# 10_POWER.net
KiCad netlist of a schematic drawn in Altium Designer
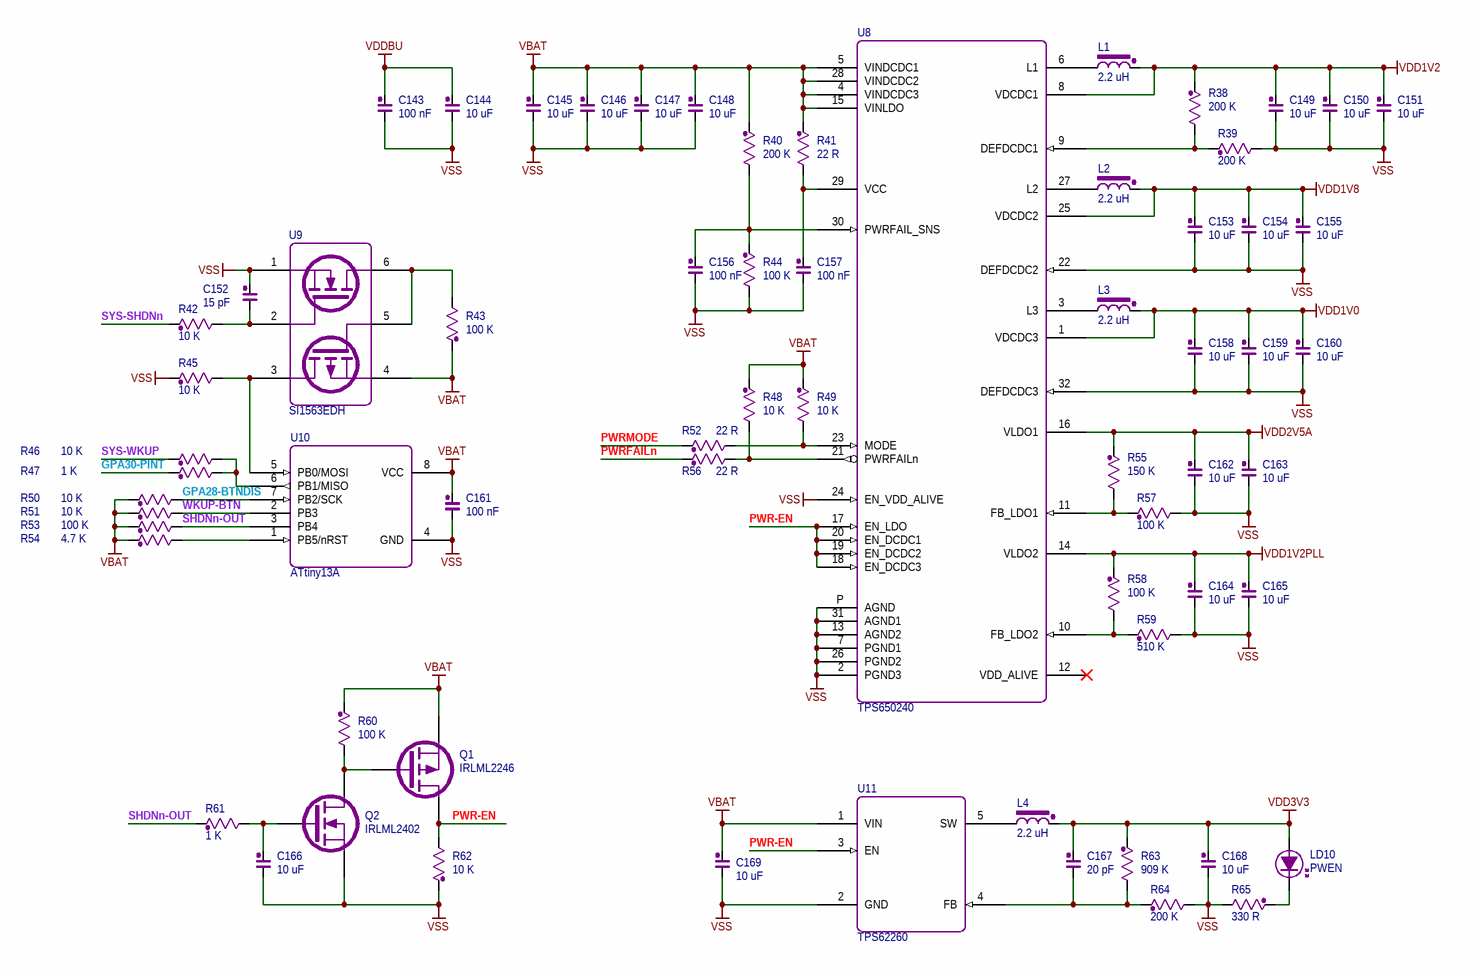
[diagram p0: 10_POWER.SchDoc]

(export (version "E")
  (design (tool "Eeschema 10.0.6"))
  (components
    (comp (ref "C143")
      (value "100 nF")
      (footprint "0402A1")
      (description "Normal Capacitor")
      (fields
        (field (name "PARTNUMBER") "0")
        (field (name "PUBLISHER") "Cowin")
        (field (name "DESIGNER") "shyul")
      )
      (libsource (lib "Basc_1_Passive") (part "CAP"))
    )
    (comp (ref "C144")
      (value "10 uF")
      (footprint "0603A1")
      (description "Normal Capacitor")
      (fields
        (field (name "PARTNUMBER") "0")
        (field (name "PUBLISHER") "Cowin")
        (field (name "DESIGNER") "shyul")
      )
      (libsource (lib "Basc_1_Passive") (part "CAP"))
    )
    (comp (ref "C145")
      (value "10 uF")
      (footprint "0603A1")
      (description "Normal Capacitor")
      (fields
        (field (name "PARTNUMBER") "0")
        (field (name "PUBLISHER") "Cowin")
        (field (name "DESIGNER") "shyul")
      )
      (libsource (lib "Basc_1_Passive") (part "CAP"))
    )
    (comp (ref "C146")
      (value "10 uF")
      (footprint "0603A1")
      (description "Normal Capacitor")
      (fields
        (field (name "PARTNUMBER") "0")
        (field (name "PUBLISHER") "Cowin")
        (field (name "DESIGNER") "shyul")
      )
      (libsource (lib "Basc_1_Passive") (part "CAP"))
    )
    (comp (ref "C147")
      (value "10 uF")
      (footprint "0603A1")
      (description "Normal Capacitor")
      (fields
        (field (name "PARTNUMBER") "0")
        (field (name "PUBLISHER") "Cowin")
        (field (name "DESIGNER") "shyul")
      )
      (libsource (lib "Basc_1_Passive") (part "CAP"))
    )
    (comp (ref "C148")
      (value "10 uF")
      (footprint "0603A1")
      (description "Normal Capacitor")
      (fields
        (field (name "PARTNUMBER") "0")
        (field (name "PUBLISHER") "Cowin")
        (field (name "DESIGNER") "shyul")
      )
      (libsource (lib "Basc_1_Passive") (part "CAP"))
    )
    (comp (ref "C149")
      (value "10 uF")
      (footprint "0603A1")
      (description "Normal Capacitor")
      (fields
        (field (name "PARTNUMBER") "0")
        (field (name "PUBLISHER") "Cowin")
        (field (name "DESIGNER") "shyul")
      )
      (libsource (lib "Basc_1_Passive") (part "CAP"))
    )
    (comp (ref "C150")
      (value "10 uF")
      (footprint "0603A1")
      (description "Normal Capacitor")
      (fields
        (field (name "PARTNUMBER") "0")
        (field (name "PUBLISHER") "Cowin")
        (field (name "DESIGNER") "shyul")
      )
      (libsource (lib "Basc_1_Passive") (part "CAP"))
    )
    (comp (ref "C151")
      (value "10 uF")
      (footprint "0603A1")
      (description "Normal Capacitor")
      (fields
        (field (name "PARTNUMBER") "0")
        (field (name "PUBLISHER") "Cowin")
        (field (name "DESIGNER") "shyul")
      )
      (libsource (lib "Basc_1_Passive") (part "CAP"))
    )
    (comp (ref "C152")
      (value "15 pF")
      (footprint "0402A1")
      (description "Normal Capacitor")
      (fields
        (field (name "PARTNUMBER") "0")
        (field (name "PUBLISHER") "Cowin")
        (field (name "DESIGNER") "shyul")
      )
      (libsource (lib "Basc_1_Passive") (part "CAP"))
    )
    (comp (ref "C153")
      (value "10 uF")
      (footprint "0603A1")
      (description "Normal Capacitor")
      (fields
        (field (name "PARTNUMBER") "0")
        (field (name "PUBLISHER") "Cowin")
        (field (name "DESIGNER") "shyul")
      )
      (libsource (lib "Basc_1_Passive") (part "CAP"))
    )
    (comp (ref "C154")
      (value "10 uF")
      (footprint "0603A1")
      (description "Normal Capacitor")
      (fields
        (field (name "PARTNUMBER") "0")
        (field (name "PUBLISHER") "Cowin")
        (field (name "DESIGNER") "shyul")
      )
      (libsource (lib "Basc_1_Passive") (part "CAP"))
    )
    (comp (ref "C155")
      (value "10 uF")
      (footprint "0603A1")
      (description "Normal Capacitor")
      (fields
        (field (name "PARTNUMBER") "0")
        (field (name "PUBLISHER") "Cowin")
        (field (name "DESIGNER") "shyul")
      )
      (libsource (lib "Basc_1_Passive") (part "CAP"))
    )
    (comp (ref "C156")
      (value "100 nF")
      (footprint "0402A1")
      (description "Normal Capacitor")
      (fields
        (field (name "PARTNUMBER") "0")
        (field (name "PUBLISHER") "Cowin")
        (field (name "DESIGNER") "shyul")
      )
      (libsource (lib "Basc_1_Passive") (part "CAP"))
    )
    (comp (ref "C157")
      (value "100 nF")
      (footprint "0402A1")
      (description "Normal Capacitor")
      (fields
        (field (name "PARTNUMBER") "0")
        (field (name "PUBLISHER") "Cowin")
        (field (name "DESIGNER") "shyul")
      )
      (libsource (lib "Basc_1_Passive") (part "CAP"))
    )
    (comp (ref "C158")
      (value "10 uF")
      (footprint "0603A1")
      (description "Normal Capacitor")
      (fields
        (field (name "PARTNUMBER") "0")
        (field (name "PUBLISHER") "Cowin")
        (field (name "DESIGNER") "shyul")
      )
      (libsource (lib "Basc_1_Passive") (part "CAP"))
    )
    (comp (ref "C159")
      (value "10 uF")
      (footprint "0603A1")
      (description "Normal Capacitor")
      (fields
        (field (name "PARTNUMBER") "0")
        (field (name "PUBLISHER") "Cowin")
        (field (name "DESIGNER") "shyul")
      )
      (libsource (lib "Basc_1_Passive") (part "CAP"))
    )
    (comp (ref "C160")
      (value "10 uF")
      (footprint "0603A1")
      (description "Normal Capacitor")
      (fields
        (field (name "PARTNUMBER") "0")
        (field (name "PUBLISHER") "Cowin")
        (field (name "DESIGNER") "shyul")
      )
      (libsource (lib "Basc_1_Passive") (part "CAP"))
    )
    (comp (ref "C161")
      (value "100 nF")
      (footprint "0402A1")
      (description "Normal Capacitor")
      (fields
        (field (name "PARTNUMBER") "0")
        (field (name "PUBLISHER") "Cowin")
        (field (name "DESIGNER") "shyul")
      )
      (libsource (lib "Basc_1_Passive") (part "CAP"))
    )
    (comp (ref "C162")
      (value "10 uF")
      (footprint "0603A1")
      (description "Normal Capacitor")
      (fields
        (field (name "PARTNUMBER") "0")
        (field (name "PUBLISHER") "Cowin")
        (field (name "DESIGNER") "shyul")
      )
      (libsource (lib "Basc_1_Passive") (part "CAP"))
    )
    (comp (ref "C163")
      (value "10 uF")
      (footprint "0603A1")
      (description "Normal Capacitor")
      (fields
        (field (name "PARTNUMBER") "0")
        (field (name "PUBLISHER") "Cowin")
        (field (name "DESIGNER") "shyul")
      )
      (libsource (lib "Basc_1_Passive") (part "CAP"))
    )
    (comp (ref "C164")
      (value "10 uF")
      (footprint "0603A1")
      (description "Normal Capacitor")
      (fields
        (field (name "PARTNUMBER") "0")
        (field (name "PUBLISHER") "Cowin")
        (field (name "DESIGNER") "shyul")
      )
      (libsource (lib "Basc_1_Passive") (part "CAP"))
    )
    (comp (ref "C165")
      (value "10 uF")
      (footprint "0603A1")
      (description "Normal Capacitor")
      (fields
        (field (name "PARTNUMBER") "0")
        (field (name "PUBLISHER") "Cowin")
        (field (name "DESIGNER") "shyul")
      )
      (libsource (lib "Basc_1_Passive") (part "CAP"))
    )
    (comp (ref "C166")
      (value "10 uF")
      (footprint "0603A1")
      (description "Normal Capacitor")
      (fields
        (field (name "PARTNUMBER") "0")
        (field (name "PUBLISHER") "Cowin")
        (field (name "DESIGNER") "shyul")
      )
      (libsource (lib "Basc_1_Passive") (part "CAP"))
    )
    (comp (ref "C167")
      (value "20 pF")
      (footprint "0402A1")
      (description "Normal Capacitor")
      (fields
        (field (name "PARTNUMBER") "0")
        (field (name "PUBLISHER") "Cowin")
        (field (name "DESIGNER") "shyul")
      )
      (libsource (lib "Basc_1_Passive") (part "CAP"))
    )
    (comp (ref "C168")
      (value "10 uF")
      (footprint "0603A1")
      (description "Normal Capacitor")
      (fields
        (field (name "PARTNUMBER") "0")
        (field (name "PUBLISHER") "Cowin")
        (field (name "DESIGNER") "shyul")
      )
      (libsource (lib "Basc_1_Passive") (part "CAP"))
    )
    (comp (ref "C169")
      (value "10 uF")
      (footprint "0603A1")
      (description "Normal Capacitor")
      (fields
        (field (name "PARTNUMBER") "0")
        (field (name "PUBLISHER") "Cowin")
        (field (name "DESIGNER") "shyul")
      )
      (libsource (lib "Basc_1_Passive") (part "CAP"))
    )
    (comp (ref "L1")
      (value "2.2 uH")
      (footprint "COIL_S_3X3")
      (description "Power Coil Inductor")
      (fields
        (field (name "PARTNUMBER") "LPD3015-222ML")
        (field (name "PUBLISHER") "Cowin")
        (field (name "DESIGNER") "shyul")
      )
      (libsource (lib "Basc_1_Passive") (part "COIL"))
    )
    (comp (ref "L2")
      (value "2.2 uH")
      (footprint "COIL_S_3X3")
      (description "Power Coil Inductor")
      (fields
        (field (name "PARTNUMBER") "LPD3015-222ML")
        (field (name "PUBLISHER") "Cowin")
        (field (name "DESIGNER") "shyul")
      )
      (libsource (lib "Basc_1_Passive") (part "COIL"))
    )
    (comp (ref "L3")
      (value "2.2 uH")
      (footprint "COIL_S_3X3")
      (description "Power Coil Inductor")
      (fields
        (field (name "PARTNUMBER") "LPD3015-222ML")
        (field (name "PUBLISHER") "Cowin")
        (field (name "DESIGNER") "shyul")
      )
      (libsource (lib "Basc_1_Passive") (part "COIL"))
    )
    (comp (ref "L4")
      (value "2.2 uH")
      (footprint "COIL_S_3X3")
      (description "Power Coil Inductor")
      (fields
        (field (name "PARTNUMBER") "LPD3015-222ML")
        (field (name "PUBLISHER") "Cowin")
        (field (name "DESIGNER") "shyul")
      )
      (libsource (lib "Basc_1_Passive") (part "COIL"))
    )
    (comp (ref "LD10")
      (value "PWEN")
      (footprint "0603LD")
      (description "LED Single")
      (fields
        (field (name "PARTNUMBER") "0")
        (field (name "DESIGNER") "shyul")
        (field (name "PUBLISHER") "Cowin")
      )
      (libsource (lib "Basc_4_Other") (part "LED"))
    )
    (comp (ref "Q1")
      (value "IRLML2246")
      (footprint "SOT-23-3")
      (description "P Channel Enhancement MOSFET")
      (fields
        (field (name "PARTNUMBER") "IRLML2246TRPbF")
        (field (name "PUBLISHER") "Cowin")
        (field (name "DESIGNER") "shyul")
      )
      (libsource (lib "Basc_3_Diode_Transistor") (part "MOSFET_EP"))
    )
    (comp (ref "Q2")
      (value "IRLML2402")
      (footprint "SOT-23-3")
      (description "N Channel Enhancement MOSFET")
      (fields
        (field (name "PARTNUMBER") "IRLML2402GPbF")
        (field (name "PUBLISHER") "Cowin")
        (field (name "DESIGNER") "shyul")
      )
      (libsource (lib "Basc_3_Diode_Transistor") (part "MOSFET_EN"))
    )
    (comp (ref "R38")
      (value "200 K")
      (footprint "0402A2")
      (description "Normal Resistor")
      (fields
        (field (name "PARTNUMBER") "0")
        (field (name "DESIGNER") "shyul")
        (field (name "PUBLISHER") "Cowin")
      )
      (libsource (lib "Basc_1_Passive") (part "RES"))
    )
    (comp (ref "R39")
      (value "200 K")
      (footprint "0402A2")
      (description "Normal Resistor")
      (fields
        (field (name "PARTNUMBER") "0")
        (field (name "DESIGNER") "shyul")
        (field (name "PUBLISHER") "Cowin")
      )
      (libsource (lib "Basc_1_Passive") (part "RES"))
    )
    (comp (ref "R40")
      (value "200 K")
      (footprint "0402A2")
      (description "Normal Resistor")
      (fields
        (field (name "PARTNUMBER") "0")
        (field (name "DESIGNER") "shyul")
        (field (name "PUBLISHER") "Cowin")
      )
      (libsource (lib "Basc_1_Passive") (part "RES"))
    )
    (comp (ref "R41")
      (value "22 R")
      (footprint "0402A2")
      (description "Normal Resistor")
      (fields
        (field (name "PARTNUMBER") "0")
        (field (name "DESIGNER") "shyul")
        (field (name "PUBLISHER") "Cowin")
      )
      (libsource (lib "Basc_1_Passive") (part "RES"))
    )
    (comp (ref "R42")
      (value "10 K")
      (footprint "0402A2")
      (description "Normal Resistor")
      (fields
        (field (name "PARTNUMBER") "0")
        (field (name "DESIGNER") "shyul")
        (field (name "PUBLISHER") "Cowin")
      )
      (libsource (lib "Basc_1_Passive") (part "RES"))
    )
    (comp (ref "R43")
      (value "100 K")
      (footprint "0402A2")
      (description "Normal Resistor")
      (fields
        (field (name "PARTNUMBER") "0")
        (field (name "DESIGNER") "shyul")
        (field (name "PUBLISHER") "Cowin")
      )
      (libsource (lib "Basc_1_Passive") (part "RES"))
    )
    (comp (ref "R44")
      (value "100 K")
      (footprint "0402A2")
      (description "Normal Resistor")
      (fields
        (field (name "PARTNUMBER") "0")
        (field (name "DESIGNER") "shyul")
        (field (name "PUBLISHER") "Cowin")
      )
      (libsource (lib "Basc_1_Passive") (part "RES"))
    )
    (comp (ref "R45")
      (value "10 K")
      (footprint "0402A2")
      (description "Normal Resistor")
      (fields
        (field (name "PARTNUMBER") "0")
        (field (name "DESIGNER") "shyul")
        (field (name "PUBLISHER") "Cowin")
      )
      (libsource (lib "Basc_1_Passive") (part "RES"))
    )
    (comp (ref "R46")
      (value "10 K")
      (footprint "0402A2")
      (description "Normal Resistor")
      (fields
        (field (name "PARTNUMBER") "0")
        (field (name "DESIGNER") "shyul")
        (field (name "PUBLISHER") "Cowin")
      )
      (libsource (lib "Basc_1_Passive") (part "RES"))
    )
    (comp (ref "R47")
      (value "1 K")
      (footprint "0402A2")
      (description "Normal Resistor")
      (fields
        (field (name "PARTNUMBER") "0")
        (field (name "DESIGNER") "shyul")
        (field (name "PUBLISHER") "Cowin")
      )
      (libsource (lib "Basc_1_Passive") (part "RES"))
    )
    (comp (ref "R48")
      (value "10 K")
      (footprint "0402A2")
      (description "Normal Resistor")
      (fields
        (field (name "PARTNUMBER") "0")
        (field (name "DESIGNER") "shyul")
        (field (name "PUBLISHER") "Cowin")
      )
      (libsource (lib "Basc_1_Passive") (part "RES"))
    )
    (comp (ref "R49")
      (value "10 K")
      (footprint "0402A2")
      (description "Normal Resistor")
      (fields
        (field (name "PARTNUMBER") "0")
        (field (name "DESIGNER") "shyul")
        (field (name "PUBLISHER") "Cowin")
      )
      (libsource (lib "Basc_1_Passive") (part "RES"))
    )
    (comp (ref "R50")
      (value "10 K")
      (footprint "0402A2")
      (description "Normal Resistor")
      (fields
        (field (name "PARTNUMBER") "0")
        (field (name "DESIGNER") "shyul")
        (field (name "PUBLISHER") "Cowin")
      )
      (libsource (lib "Basc_1_Passive") (part "RES"))
    )
    (comp (ref "R51")
      (value "10 K")
      (footprint "0402A2")
      (description "Normal Resistor")
      (fields
        (field (name "PARTNUMBER") "0")
        (field (name "DESIGNER") "shyul")
        (field (name "PUBLISHER") "Cowin")
      )
      (libsource (lib "Basc_1_Passive") (part "RES"))
    )
    (comp (ref "R52")
      (value "22 R")
      (footprint "0402A2")
      (description "Normal Resistor")
      (fields
        (field (name "PARTNUMBER") "0")
        (field (name "DESIGNER") "shyul")
        (field (name "PUBLISHER") "Cowin")
      )
      (libsource (lib "Basc_1_Passive") (part "RES"))
    )
    (comp (ref "R53")
      (value "100 K")
      (footprint "0402A2")
      (description "Normal Resistor")
      (fields
        (field (name "PARTNUMBER") "0")
        (field (name "DESIGNER") "shyul")
        (field (name "PUBLISHER") "Cowin")
      )
      (libsource (lib "Basc_1_Passive") (part "RES"))
    )
    (comp (ref "R54")
      (value "4.7 K")
      (footprint "0402A2")
      (description "Normal Resistor")
      (fields
        (field (name "PARTNUMBER") "0")
        (field (name "DESIGNER") "shyul")
        (field (name "PUBLISHER") "Cowin")
      )
      (libsource (lib "Basc_1_Passive") (part "RES"))
    )
    (comp (ref "R55")
      (value "150 K")
      (footprint "0402A2")
      (description "Normal Resistor")
      (fields
        (field (name "PARTNUMBER") "0")
        (field (name "DESIGNER") "shyul")
        (field (name "PUBLISHER") "Cowin")
      )
      (libsource (lib "Basc_1_Passive") (part "RES"))
    )
    (comp (ref "R56")
      (value "22 R")
      (footprint "0402A2")
      (description "Normal Resistor")
      (fields
        (field (name "PARTNUMBER") "0")
        (field (name "DESIGNER") "shyul")
        (field (name "PUBLISHER") "Cowin")
      )
      (libsource (lib "Basc_1_Passive") (part "RES"))
    )
    (comp (ref "R57")
      (value "100 K")
      (footprint "0402A2")
      (description "Normal Resistor")
      (fields
        (field (name "PARTNUMBER") "0")
        (field (name "DESIGNER") "shyul")
        (field (name "PUBLISHER") "Cowin")
      )
      (libsource (lib "Basc_1_Passive") (part "RES"))
    )
    (comp (ref "R58")
      (value "100 K")
      (footprint "0402A2")
      (description "Normal Resistor")
      (fields
        (field (name "PARTNUMBER") "0")
        (field (name "DESIGNER") "shyul")
        (field (name "PUBLISHER") "Cowin")
      )
      (libsource (lib "Basc_1_Passive") (part "RES"))
    )
    (comp (ref "R59")
      (value "510 K")
      (footprint "0402A2")
      (description "Normal Resistor")
      (fields
        (field (name "PARTNUMBER") "0")
        (field (name "DESIGNER") "shyul")
        (field (name "PUBLISHER") "Cowin")
      )
      (libsource (lib "Basc_1_Passive") (part "RES"))
    )
    (comp (ref "R60")
      (value "100 K")
      (footprint "0402A2")
      (description "Normal Resistor")
      (fields
        (field (name "PARTNUMBER") "0")
        (field (name "DESIGNER") "shyul")
        (field (name "PUBLISHER") "Cowin")
      )
      (libsource (lib "Basc_1_Passive") (part "RES"))
    )
    (comp (ref "R61")
      (value "1 K")
      (footprint "0402A2")
      (description "Normal Resistor")
      (fields
        (field (name "PARTNUMBER") "0")
        (field (name "DESIGNER") "shyul")
        (field (name "PUBLISHER") "Cowin")
      )
      (libsource (lib "Basc_1_Passive") (part "RES"))
    )
    (comp (ref "R62")
      (value "10 K")
      (footprint "0402A2")
      (description "Normal Resistor")
      (fields
        (field (name "PARTNUMBER") "0")
        (field (name "DESIGNER") "shyul")
        (field (name "PUBLISHER") "Cowin")
      )
      (libsource (lib "Basc_1_Passive") (part "RES"))
    )
    (comp (ref "R63")
      (value "909 K")
      (footprint "0402A2")
      (description "Normal Resistor")
      (fields
        (field (name "PARTNUMBER") "0")
        (field (name "DESIGNER") "shyul")
        (field (name "PUBLISHER") "Cowin")
      )
      (libsource (lib "Basc_1_Passive") (part "RES"))
    )
    (comp (ref "R64")
      (value "200 K")
      (footprint "0402A2")
      (description "Normal Resistor")
      (fields
        (field (name "PARTNUMBER") "0")
        (field (name "DESIGNER") "shyul")
        (field (name "PUBLISHER") "Cowin")
      )
      (libsource (lib "Basc_1_Passive") (part "RES"))
    )
    (comp (ref "R65")
      (value "330 R")
      (footprint "0402A2")
      (description "Normal Resistor")
      (fields
        (field (name "PARTNUMBER") "0")
        (field (name "DESIGNER") "shyul")
        (field (name "PUBLISHER") "Cowin")
      )
      (libsource (lib "Basc_1_Passive") (part "RES"))
    )
    (comp (ref "U8")
      (value "TPS650240")
      (footprint "QFN-5-32")
      (description "Embedded Power Management IC")
      (fields
        (field (name "PARTNUMBER") "TPS650240RHBT")
        (field (name "PUBLISHER") "Cowin")
        (field (name "DESIGNER") "shyul")
      )
      (libsource (lib "PCB_XEM-S91") (part "TPS650240"))
    )
    (comp (ref "U9")
      (value "SI1563EDH")
      (footprint "SOT-363")
      (description "Complementary MOSFET")
      (fields (field (name "PUBLISHER") "Cowin") (field (name "DESIGNER") "shyul"))
      (libsource (lib "PCB_XEM-S91") (part "SI1563EDH"))
    )
    (comp (ref "U10")
      (value "ATtiny13A")
      (footprint "SOIC-8W")
      (description "Atmel SPI Flash")
      (fields
        (field (name "PARTNUMBER") "ATtiny13A-SH")
        (field (name "PUBLISHER") "Cowin")
        (field (name "DESIGNER") "shyul")
      )
      (libsource (lib "PCB_XEM-S91") (part "ATtiny13A"))
    )
    (comp (ref "U11")
      (value "TPS62260")
      (footprint "SOT-23-5")
      (description "Simple Switch 600mA Adjustable")
      (fields
        (field (name "PARTNUMBER") "TPS62260DDCR")
        (field (name "PUBLISHER") "Cowin")
        (field (name "DESIGNER") "shyul")
      )
      (libsource (lib "PCB_XEM-S91") (part "TPS62260"))
    )
  )
  (nets
    (net (code "1") (name "/GPA28-BTNDIS") (class "Default")
      (node (ref "R50") (pin "1") (pinfunction "1_1") (pintype "passive"))
      (node (ref "U10") (pin "7") (pinfunction "PB2/SCK_7") (pintype "input"))
    )
    (net (code "2") (name "/GPA30-PINT") (class "Default")
      (node (ref "R47") (pin "2") (pinfunction "2_2") (pintype "passive"))
    )
    (net (code "3") (name "/PWR-EN") (class "Default")
      (node (ref "Q1") (pin "2") (pinfunction "D_2") (pintype "passive"))
      (node (ref "R62") (pin "1") (pinfunction "1_1") (pintype "passive"))
      (node (ref "U11") (pin "3") (pinfunction "EN_3") (pintype "input"))
      (node (ref "U8") (pin "17") (pinfunction "EN_LDO_17") (pintype "input"))
      (node (ref "U8") (pin "18") (pinfunction "EN_DCDC3_18") (pintype "input"))
      (node (ref "U8") (pin "19") (pinfunction "EN_DCDC2_19") (pintype "input"))
      (node (ref "U8") (pin "20") (pinfunction "EN_DCDC1_20") (pintype "input"))
    )
    (net (code "4") (name "/PWRFAILn") (class "Default")
      (node (ref "R56") (pin "2") (pinfunction "2_2") (pintype "passive"))
    )
    (net (code "5") (name "/PWRMODE") (class "Default")
      (node (ref "R52") (pin "2") (pinfunction "2_2") (pintype "passive"))
    )
    (net (code "6") (name "/SHDNn-OUT") (class "Default")
      (node (ref "R53") (pin "1") (pinfunction "1_1") (pintype "passive"))
      (node (ref "R61") (pin "2") (pinfunction "2_2") (pintype "passive"))
      (node (ref "U10") (pin "3") (pinfunction "PB4_3") (pintype "passive"))
    )
    (net (code "7") (name "/SYS-SHDNn") (class "Default")
      (node (ref "R42") (pin "2") (pinfunction "2_2") (pintype "passive"))
    )
    (net (code "8") (name "/SYS-WKUP") (class "Default")
      (node (ref "R46") (pin "2") (pinfunction "2_2") (pintype "passive"))
    )
    (net (code "9") (name "/WKUP-BTN") (class "Default")
      (node (ref "R51") (pin "1") (pinfunction "1_1") (pintype "passive"))
      (node (ref "U10") (pin "2") (pinfunction "PB3_2") (pintype "passive"))
    )
    (net (code "10") (name "Net-(C152-Pad1)") (class "Default")
      (node (ref "C152") (pin "1") (pinfunction "1_1") (pintype "passive"))
      (node (ref "R42") (pin "1") (pinfunction "1_1") (pintype "passive"))
      (node (ref "U9") (pin "2") (pinfunction "2_2") (pintype "passive"))
    )
    (net (code "11") (name "Net-(LD10-Pad1)") (class "Default")
      (node (ref "LD10") (pin "1") (pinfunction "1_1") (pintype "passive"))
      (node (ref "R65") (pin "2") (pinfunction "2_2") (pintype "passive"))
    )
    (net (code "12") (name "Net-(Q1-G)") (class "Default")
      (node (ref "Q1") (pin "1") (pinfunction "G_1") (pintype "passive"))
      (node (ref "Q2") (pin "2") (pinfunction "D_2") (pintype "passive"))
      (node (ref "R60") (pin "1") (pinfunction "1_1") (pintype "passive"))
    )
    (net (code "13") (name "Net-(Q2-G)") (class "Default")
      (node (ref "C166") (pin "2") (pinfunction "2_2") (pintype "passive"))
      (node (ref "Q2") (pin "1") (pinfunction "G_1") (pintype "passive"))
      (node (ref "R61") (pin "1") (pinfunction "1_1") (pintype "passive"))
    )
    (net (code "14") (name "Net-(R43-Pad1)") (class "Default")
      (node (ref "R43") (pin "1") (pinfunction "1_1") (pintype "passive"))
      (node (ref "U9") (pin "5") (pinfunction "5_5") (pintype "passive"))
      (node (ref "U9") (pin "6") (pinfunction "6_6") (pintype "passive"))
    )
    (net (code "15") (name "Net-(U8-DEFDCDC1)") (class "Default")
      (node (ref "R38") (pin "1") (pinfunction "1_1") (pintype "passive"))
      (node (ref "R39") (pin "2") (pinfunction "2_2") (pintype "passive"))
      (node (ref "U8") (pin "9") (pinfunction "DEFDCDC1_9") (pintype "input"))
    )
    (net (code "16") (name "Net-(U8-FB_LDO1)") (class "Default")
      (node (ref "R55") (pin "1") (pinfunction "1_1") (pintype "passive"))
      (node (ref "R57") (pin "2") (pinfunction "2_2") (pintype "passive"))
      (node (ref "U8") (pin "11") (pinfunction "FB_LDO1_11") (pintype "input"))
    )
    (net (code "17") (name "Net-(U8-FB_LDO2)") (class "Default")
      (node (ref "R58") (pin "1") (pinfunction "1_1") (pintype "passive"))
      (node (ref "R59") (pin "2") (pinfunction "2_2") (pintype "passive"))
      (node (ref "U8") (pin "10") (pinfunction "FB_LDO2_10") (pintype "input"))
    )
    (net (code "18") (name "Net-(U8-L1)") (class "Default")
      (node (ref "L1") (pin "1") (pinfunction "1_1") (pintype "passive"))
      (node (ref "U8") (pin "6") (pinfunction "L1_6") (pintype "power_in"))
    )
    (net (code "19") (name "Net-(U8-L2)") (class "Default")
      (node (ref "L2") (pin "1") (pinfunction "1_1") (pintype "passive"))
      (node (ref "U8") (pin "27") (pinfunction "L2_27") (pintype "power_in"))
    )
    (net (code "20") (name "Net-(U8-L3)") (class "Default")
      (node (ref "L3") (pin "1") (pinfunction "1_1") (pintype "passive"))
      (node (ref "U8") (pin "3") (pinfunction "L3_3") (pintype "power_in"))
    )
    (net (code "21") (name "Net-(U8-MODE)") (class "Default")
      (node (ref "R49") (pin "1") (pinfunction "1_1") (pintype "passive"))
      (node (ref "R52") (pin "1") (pinfunction "1_1") (pintype "passive"))
      (node (ref "U8") (pin "23") (pinfunction "MODE_23") (pintype "input"))
    )
    (net (code "22") (name "Net-(U8-PWRFAIL_SNS)") (class "Default")
      (node (ref "C156") (pin "2") (pinfunction "2_2") (pintype "passive"))
      (node (ref "R40") (pin "1") (pinfunction "1_1") (pintype "passive"))
      (node (ref "R44") (pin "2") (pinfunction "2_2") (pintype "passive"))
      (node (ref "U8") (pin "30") (pinfunction "PWRFAIL_SNS_30") (pintype "input"))
    )
    (net (code "23") (name "Net-(U8-PWRFAILn)") (class "Default")
      (node (ref "R48") (pin "1") (pinfunction "1_1") (pintype "passive"))
      (node (ref "R56") (pin "1") (pinfunction "1_1") (pintype "passive"))
      (node (ref "U8") (pin "21") (pinfunction "PWRFAILn_21") (pintype "output"))
    )
    (net (code "24") (name "Net-(U8-VCC)") (class "Default")
      (node (ref "C157") (pin "2") (pinfunction "2_2") (pintype "passive"))
      (node (ref "R41") (pin "1") (pinfunction "1_1") (pintype "passive"))
      (node (ref "U8") (pin "29") (pinfunction "VCC_29") (pintype "passive"))
    )
    (net (code "25") (name "Net-(U10-PB0{slash}MOSI)") (class "Default")
      (node (ref "R45") (pin "1") (pinfunction "1_1") (pintype "passive"))
      (node (ref "U10") (pin "5") (pinfunction "PB0/MOSI_5") (pintype "input"))
      (node (ref "U9") (pin "3") (pinfunction "3_3") (pintype "passive"))
    )
    (net (code "26") (name "Net-(U10-PB1{slash}MISO)") (class "Default")
      (node (ref "R46") (pin "1") (pinfunction "1_1") (pintype "passive"))
      (node (ref "R47") (pin "1") (pinfunction "1_1") (pintype "passive"))
      (node (ref "U10") (pin "6") (pinfunction "PB1/MISO_6") (pintype "output"))
    )
    (net (code "27") (name "Net-(U10-PB5{slash}nRST)") (class "Default")
      (node (ref "R54") (pin "1") (pinfunction "1_1") (pintype "passive"))
      (node (ref "U10") (pin "1") (pinfunction "PB5/nRST_1") (pintype "input"))
    )
    (net (code "28") (name "Net-(U11-FB)") (class "Default")
      (node (ref "C167") (pin "1") (pinfunction "1_1") (pintype "passive"))
      (node (ref "R63") (pin "1") (pinfunction "1_1") (pintype "passive"))
      (node (ref "R64") (pin "2") (pinfunction "2_2") (pintype "passive"))
      (node (ref "U11") (pin "4") (pinfunction "FB_4") (pintype "input"))
    )
    (net (code "29") (name "Net-(U11-SW)") (class "Default")
      (node (ref "L4") (pin "1") (pinfunction "1_1") (pintype "passive"))
      (node (ref "U11") (pin "5") (pinfunction "SW_5") (pintype "power_in"))
    )
    (net (code "30") (name "VBAT") (class "Default")
      (node (ref "C145") (pin "2") (pinfunction "2_2") (pintype "passive"))
      (node (ref "C146") (pin "2") (pinfunction "2_2") (pintype "passive"))
      (node (ref "C147") (pin "2") (pinfunction "2_2") (pintype "passive"))
      (node (ref "C148") (pin "2") (pinfunction "2_2") (pintype "passive"))
      (node (ref "C161") (pin "2") (pinfunction "2_2") (pintype "passive"))
      (node (ref "C169") (pin "2") (pinfunction "2_2") (pintype "passive"))
      (node (ref "Q1") (pin "3") (pinfunction "S_3") (pintype "passive"))
      (node (ref "R40") (pin "2") (pinfunction "2_2") (pintype "passive"))
      (node (ref "R41") (pin "2") (pinfunction "2_2") (pintype "passive"))
      (node (ref "R43") (pin "2") (pinfunction "2_2") (pintype "passive"))
      (node (ref "R48") (pin "2") (pinfunction "2_2") (pintype "passive"))
      (node (ref "R49") (pin "2") (pinfunction "2_2") (pintype "passive"))
      (node (ref "R50") (pin "2") (pinfunction "2_2") (pintype "passive"))
      (node (ref "R51") (pin "2") (pinfunction "2_2") (pintype "passive"))
      (node (ref "R53") (pin "2") (pinfunction "2_2") (pintype "passive"))
      (node (ref "R54") (pin "2") (pinfunction "2_2") (pintype "passive"))
      (node (ref "R60") (pin "2") (pinfunction "2_2") (pintype "passive"))
      (node (ref "U10") (pin "8") (pinfunction "VCC_8") (pintype "passive"))
      (node (ref "U11") (pin "1") (pinfunction "VIN_1") (pintype "passive"))
      (node (ref "U8") (pin "15") (pinfunction "VINLDO_15") (pintype "passive"))
      (node (ref "U8") (pin "28") (pinfunction "VINDCDC2_28") (pintype "passive"))
      (node (ref "U8") (pin "4") (pinfunction "VINDCDC3_4") (pintype "passive"))
      (node (ref "U8") (pin "5") (pinfunction "VINDCDC1_5") (pintype "passive"))
      (node (ref "U9") (pin "4") (pinfunction "4_4") (pintype "passive"))
    )
    (net (code "31") (name "VDD1V0") (class "Default")
      (node (ref "C158") (pin "2") (pinfunction "2_2") (pintype "passive"))
      (node (ref "C159") (pin "2") (pinfunction "2_2") (pintype "passive"))
      (node (ref "C160") (pin "2") (pinfunction "2_2") (pintype "passive"))
      (node (ref "L3") (pin "2") (pinfunction "2_2") (pintype "passive"))
      (node (ref "U8") (pin "1") (pinfunction "VDCDC3_1") (pintype "power_in"))
    )
    (net (code "32") (name "VDD1V2") (class "Default")
      (node (ref "C149") (pin "2") (pinfunction "2_2") (pintype "passive"))
      (node (ref "C150") (pin "2") (pinfunction "2_2") (pintype "passive"))
      (node (ref "C151") (pin "2") (pinfunction "2_2") (pintype "passive"))
      (node (ref "L1") (pin "2") (pinfunction "2_2") (pintype "passive"))
      (node (ref "R38") (pin "2") (pinfunction "2_2") (pintype "passive"))
      (node (ref "U8") (pin "8") (pinfunction "VDCDC1_8") (pintype "power_in"))
    )
    (net (code "33") (name "VDD1V2PLL") (class "Default")
      (node (ref "C164") (pin "2") (pinfunction "2_2") (pintype "passive"))
      (node (ref "C165") (pin "2") (pinfunction "2_2") (pintype "passive"))
      (node (ref "R58") (pin "2") (pinfunction "2_2") (pintype "passive"))
      (node (ref "U8") (pin "14") (pinfunction "VLDO2_14") (pintype "power_in"))
    )
    (net (code "34") (name "VDD1V8") (class "Default")
      (node (ref "C153") (pin "2") (pinfunction "2_2") (pintype "passive"))
      (node (ref "C154") (pin "2") (pinfunction "2_2") (pintype "passive"))
      (node (ref "C155") (pin "2") (pinfunction "2_2") (pintype "passive"))
      (node (ref "L2") (pin "2") (pinfunction "2_2") (pintype "passive"))
      (node (ref "U8") (pin "25") (pinfunction "VDCDC2_25") (pintype "power_in"))
    )
    (net (code "35") (name "VDD2V5A") (class "Default")
      (node (ref "C162") (pin "2") (pinfunction "2_2") (pintype "passive"))
      (node (ref "C163") (pin "2") (pinfunction "2_2") (pintype "passive"))
      (node (ref "R55") (pin "2") (pinfunction "2_2") (pintype "passive"))
      (node (ref "U8") (pin "16") (pinfunction "VLDO1_16") (pintype "power_in"))
    )
    (net (code "36") (name "VDD3V3") (class "Default")
      (node (ref "C167") (pin "2") (pinfunction "2_2") (pintype "passive"))
      (node (ref "C168") (pin "2") (pinfunction "2_2") (pintype "passive"))
      (node (ref "L4") (pin "2") (pinfunction "2_2") (pintype "passive"))
      (node (ref "LD10") (pin "2") (pinfunction "2_2") (pintype "passive"))
      (node (ref "R63") (pin "2") (pinfunction "2_2") (pintype "passive"))
    )
    (net (code "37") (name "VDDBU") (class "Default")
      (node (ref "C143") (pin "2") (pinfunction "2_2") (pintype "passive"))
      (node (ref "C144") (pin "2") (pinfunction "2_2") (pintype "passive"))
    )
    (net (code "38") (name "VSS") (class "Default")
      (node (ref "C143") (pin "1") (pinfunction "1_1") (pintype "passive"))
      (node (ref "C144") (pin "1") (pinfunction "1_1") (pintype "passive"))
      (node (ref "C145") (pin "1") (pinfunction "1_1") (pintype "passive"))
      (node (ref "C146") (pin "1") (pinfunction "1_1") (pintype "passive"))
      (node (ref "C147") (pin "1") (pinfunction "1_1") (pintype "passive"))
      (node (ref "C148") (pin "1") (pinfunction "1_1") (pintype "passive"))
      (node (ref "C149") (pin "1") (pinfunction "1_1") (pintype "passive"))
      (node (ref "C150") (pin "1") (pinfunction "1_1") (pintype "passive"))
      (node (ref "C151") (pin "1") (pinfunction "1_1") (pintype "passive"))
      (node (ref "C152") (pin "2") (pinfunction "2_2") (pintype "passive"))
      (node (ref "C153") (pin "1") (pinfunction "1_1") (pintype "passive"))
      (node (ref "C154") (pin "1") (pinfunction "1_1") (pintype "passive"))
      (node (ref "C155") (pin "1") (pinfunction "1_1") (pintype "passive"))
      (node (ref "C156") (pin "1") (pinfunction "1_1") (pintype "passive"))
      (node (ref "C157") (pin "1") (pinfunction "1_1") (pintype "passive"))
      (node (ref "C158") (pin "1") (pinfunction "1_1") (pintype "passive"))
      (node (ref "C159") (pin "1") (pinfunction "1_1") (pintype "passive"))
      (node (ref "C160") (pin "1") (pinfunction "1_1") (pintype "passive"))
      (node (ref "C161") (pin "1") (pinfunction "1_1") (pintype "passive"))
      (node (ref "C162") (pin "1") (pinfunction "1_1") (pintype "passive"))
      (node (ref "C163") (pin "1") (pinfunction "1_1") (pintype "passive"))
      (node (ref "C164") (pin "1") (pinfunction "1_1") (pintype "passive"))
      (node (ref "C165") (pin "1") (pinfunction "1_1") (pintype "passive"))
      (node (ref "C166") (pin "1") (pinfunction "1_1") (pintype "passive"))
      (node (ref "C168") (pin "1") (pinfunction "1_1") (pintype "passive"))
      (node (ref "C169") (pin "1") (pinfunction "1_1") (pintype "passive"))
      (node (ref "Q2") (pin "3") (pinfunction "S_3") (pintype "passive"))
      (node (ref "R39") (pin "1") (pinfunction "1_1") (pintype "passive"))
      (node (ref "R44") (pin "1") (pinfunction "1_1") (pintype "passive"))
      (node (ref "R45") (pin "2") (pinfunction "2_2") (pintype "passive"))
      (node (ref "R57") (pin "1") (pinfunction "1_1") (pintype "passive"))
      (node (ref "R59") (pin "1") (pinfunction "1_1") (pintype "passive"))
      (node (ref "R62") (pin "2") (pinfunction "2_2") (pintype "passive"))
      (node (ref "R64") (pin "1") (pinfunction "1_1") (pintype "passive"))
      (node (ref "R65") (pin "1") (pinfunction "1_1") (pintype "passive"))
      (node (ref "U10") (pin "4") (pinfunction "GND_4") (pintype "passive"))
      (node (ref "U11") (pin "2") (pinfunction "GND_2") (pintype "passive"))
      (node (ref "U8") (pin "13") (pinfunction "AGND2_13") (pintype "power_in"))
      (node (ref "U8") (pin "2") (pinfunction "PGND3_2") (pintype "power_in"))
      (node (ref "U8") (pin "22") (pinfunction "DEFDCDC2_22") (pintype "input"))
      (node (ref "U8") (pin "24") (pinfunction "EN_VDD_ALIVE_24") (pintype "input"))
      (node (ref "U8") (pin "26") (pinfunction "PGND2_26") (pintype "power_in"))
      (node (ref "U8") (pin "31") (pinfunction "AGND1_31") (pintype "power_in"))
      (node (ref "U8") (pin "32") (pinfunction "DEFDCDC3_32") (pintype "input"))
      (node (ref "U8") (pin "7") (pinfunction "PGND1_7") (pintype "power_in"))
      (node (ref "U8") (pin "P") (pinfunction "AGND_P") (pintype "power_in"))
      (node (ref "U9") (pin "1") (pinfunction "1_1") (pintype "passive"))
    )
    (net (code "39") (name "unconnected-(U8-VDD_ALIVE-Pad12)") (class "Default")
      (node (ref "U8") (pin "12") (pinfunction "VDD_ALIVE_12") (pintype "power_in+no_connect"))
    )
  )
)
